# USB.net
KiCad netlist of a schematic drawn in Altium Designer
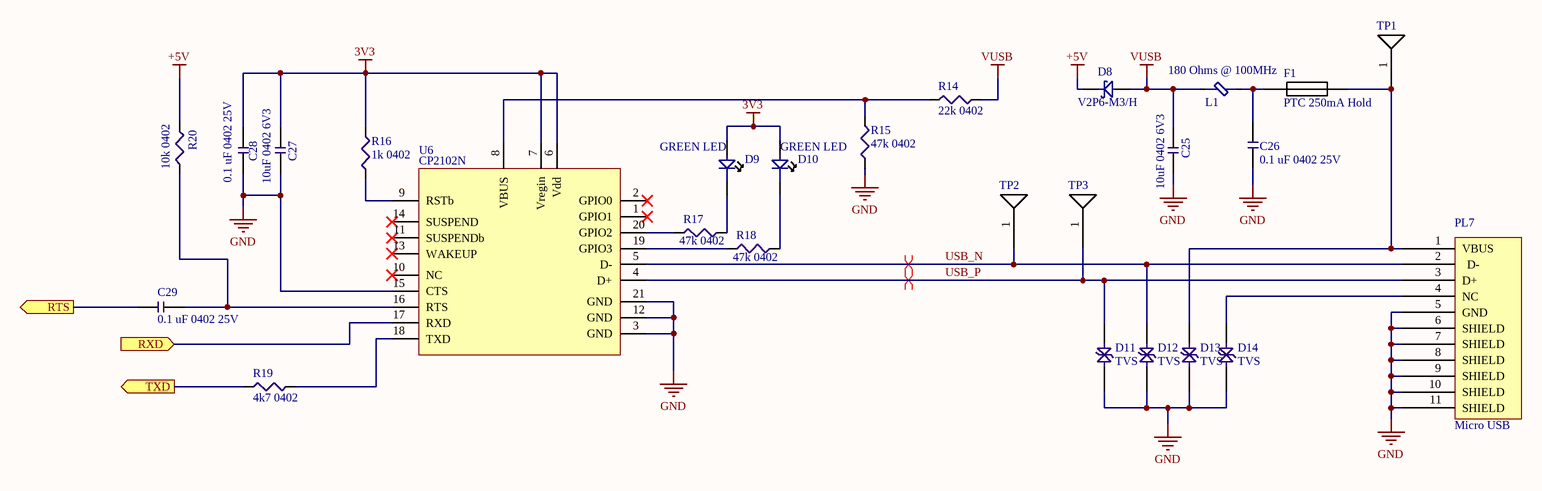
[diagram p0: USB.SchDoc]

(export (version "E")
  (design (tool "Eeschema 10.0.6"))
  (components
    (comp (ref "C25")
      (value "10uF 0402 6V3")
      (footprint "CAP_0402")
      (description "10uF 20% 0402 6V3 X6S")
      (fields (field (name "TOLERANCE") "20%") (field (name "VOLTAGE") "6V3"))
      (libsource (lib "ON Development Vault") (part "Capacitor"))
    )
    (comp (ref "C26")
      (value "0.1 uF 0402 25V")
      (footprint "CAP_0402")
      (description "0.1UF 25V 10% X5R 0402")
      (fields (field (name "TOLERANCE") "10%") (field (name "VOLTAGE") "25V"))
      (libsource (lib "ON Development Vault") (part "Capacitor"))
    )
    (comp (ref "C27")
      (value "10uF 0402 6V3")
      (footprint "CAP_0402")
      (description "10uF 20% 0402 6V3 X6S")
      (fields (field (name "TOLERANCE") "20%") (field (name "VOLTAGE") "6V3"))
      (libsource (lib "ON Development Vault") (part "Capacitor"))
    )
    (comp (ref "C28")
      (value "0.1 uF 0402 25V")
      (footprint "CAP_0402")
      (description "0.1UF 25V 10% X5R 0402")
      (fields (field (name "TOLERANCE") "10%") (field (name "VOLTAGE") "25V"))
      (libsource (lib "ON Development Vault") (part "Capacitor"))
    )
    (comp (ref "C29")
      (value "0.1 uF 0402 25V")
      (footprint "CAP_0402")
      (description "0.1UF 25V 10% X5R 0402")
      (fields (field (name "TOLERANCE") "10%") (field (name "VOLTAGE") "25V"))
      (libsource (lib "ON Development Vault") (part "Capacitor"))
    )
    (comp (ref "D8")
      (value "V2P6-M3/H")
      (footprint "MicroSMP")
      (description "DIODE SCHOTTKY 60V 2A MICROSMP")
      (libsource (lib "ON Development Vault") (part "Schottky"))
    )
    (comp (ref "D9")
      (value "GREEN LED")
      (footprint "0402 LED")
      (description "0402 SMD LED")
      (fields (field (name "MFG. PART NUMBER") "LTST-C281KGKT"))
      (libsource (lib "ON Development Vault") (part "LED"))
    )
    (comp (ref "D10")
      (value "GREEN LED")
      (footprint "0402 LED")
      (description "0402 SMD LED")
      (fields (field (name "MFG. PART NUMBER") "LTST-C281KGKT"))
      (libsource (lib "ON Development Vault") (part "LED"))
    )
    (comp (ref "D11")
      (value "TVS")
      (footprint "RES_0402")
      (description "TVS DIODE 12VC 8A IPP 0402")
      (fields (field (name "MFG. PART NUMBER") "GG040205100N2P"))
      (libsource (lib "ON Development Vault") (part "TVS"))
    )
    (comp (ref "D12")
      (value "TVS")
      (footprint "RES_0402")
      (description "TVS DIODE 12VC 8A IPP 0402")
      (fields (field (name "MFG. PART NUMBER") "GG040205100N2P"))
      (libsource (lib "ON Development Vault") (part "TVS"))
    )
    (comp (ref "D13")
      (value "TVS")
      (footprint "RES_0402")
      (description "TVS DIODE 12VC 8A IPP 0402")
      (fields (field (name "MFG. PART NUMBER") "GG040205100N2P"))
      (libsource (lib "ON Development Vault") (part "TVS"))
    )
    (comp (ref "D14")
      (value "TVS")
      (footprint "RES_0402")
      (description "TVS DIODE 12VC 8A IPP 0402")
      (fields (field (name "MFG. PART NUMBER") "GG040205100N2P"))
      (libsource (lib "ON Development Vault") (part "TVS"))
    )
    (comp (ref "F1")
      (value "PTC 250mA Hold")
      (footprint "PTC Fuse 1206")
      (description "PTC RESET FUSE 24V 250MA 1206")
      (fields (field (name "MFG. PART NUMBER") "0ZCJ0025AF2E"))
      (libsource (lib "ON Development Vault") (part "Fuse"))
    )
    (comp (ref "L1")
      (value "180 Ohms @ 100MHz")
      (footprint "IND_0603")
      (description "FERRITE BEAD 180 OHM 0603 1LN")
      (fields (field (name "MFG. PART NUMBER") "BLM18PG181SN1D"))
      (libsource (lib "ON Development Vault") (part "Ferrite"))
    )
    (comp (ref "PL7")
      (value "Micro USB")
      (footprint "10118193-0001LF Micro USB")
      (description "CONN USB MICRO B RECPT SMT R/A")
      (fields (field (name "MFG. PART NUMBER") "10118193-0001LF"))
      (libsource (lib "ON Development Vault") (part "USB 2.0 Micro usb type B header"))
    )
    (comp (ref "R14")
      (value "22k 0402")
      (footprint "RES_0402")
      (description "RES SMD 22K OHM 1% 1/16W 0402")
      (fields (field (name "POWER") "1/16W") (field (name "TOLERANCE") "1%"))
      (libsource (lib "ON Development Vault") (part "Resistor"))
    )
    (comp (ref "R15")
      (value "47k 0402")
      (footprint "RES_0402")
      (description "RES SMD 47K OHM 1% 1/16W 0402")
      (fields (field (name "POWER") "1/16W") (field (name "TOLERANCE") "1%"))
      (libsource (lib "ON Development Vault") (part "Resistor"))
    )
    (comp (ref "R16")
      (value "1k 0402")
      (footprint "RES_0402")
      (description "RES SMD 1K OHM 1% 1/16W 0402")
      (fields (field (name "POWER") "1/16W") (field (name "TOLERANCE") "1%"))
      (libsource (lib "ON Development Vault") (part "Resistor"))
    )
    (comp (ref "R17")
      (value "47k 0402")
      (footprint "RES_0402")
      (description "RES SMD 47K OHM 1% 1/16W 0402")
      (fields (field (name "POWER") "1/16W") (field (name "TOLERANCE") "1%"))
      (libsource (lib "ON Development Vault") (part "Resistor"))
    )
    (comp (ref "R18")
      (value "47k 0402")
      (footprint "RES_0402")
      (description "RES SMD 47K OHM 1% 1/16W 0402")
      (fields (field (name "POWER") "1/16W") (field (name "TOLERANCE") "1%"))
      (libsource (lib "ON Development Vault") (part "Resistor"))
    )
    (comp (ref "R19")
      (value "4k7 0402")
      (footprint "RES_0402")
      (description "RES SMD 4.7K OHM 1% 1/16W 0402")
      (fields (field (name "POWER") "1/16W") (field (name "TOLERANCE") "1"))
      (libsource (lib "ON Development Vault") (part "Resistor"))
    )
    (comp (ref "R20")
      (value "10k 0402")
      (footprint "RES_0402")
      (description "RES SMD 10K OHM 1% 1/16W 0402")
      (fields (field (name "POWER") "1/16 W") (field (name "TOLERANCE") "1 %"))
      (libsource (lib "ON Development Vault") (part "Resistor"))
    )
    (comp (ref "TP1")
      (value "TestPoint")
      (footprint "1x0mm")
      (description "Testpoint")
      (libsource (lib "ON Development Vault") (part "CMP-ROOT-0006-0.0"))
    )
    (comp (ref "TP2")
      (value "TestPoint")
      (footprint "1x0mm")
      (description "Testpoint")
      (libsource (lib "ON Development Vault") (part "CMP-ROOT-0006-0.0"))
    )
    (comp (ref "TP3")
      (value "TestPoint")
      (footprint "1x0mm")
      (description "Testpoint")
      (libsource (lib "ON Development Vault") (part "CMP-ROOT-0006-0.0"))
    )
    (comp (ref "U6")
      (value "CP2102N")
      (footprint "QFN50P300X300X80_HS-21N")
      (description "IC BRIDGE USB TO UART 20QFN")
      (fields (field (name "MFG. PART NUMBER") "CP2102N-A01-GQFN20"))
      (libsource (lib "ON Development Vault") (part "CP2102N-A01-GQFN20"))
    )
  )
  (nets
    (net (code "1") (name "+5V") (class "Default")
      (node (ref "D8") (pin "2") (pinfunction "2_2") (pintype "passive"))
      (node (ref "R20") (pin "2") (pinfunction "2_2") (pintype "passive"))
    )
    (net (code "2") (name "/RTS") (class "Default")
      (node (ref "C29") (pin "2") (pinfunction "2_2") (pintype "passive"))
    )
    (net (code "3") (name "/RXD") (class "Default")
      (node (ref "U6") (pin "17") (pinfunction "RXD_17") (pintype "passive"))
    )
    (net (code "4") (name "/TXD") (class "Default")
      (node (ref "R19") (pin "2") (pinfunction "2_2") (pintype "passive"))
    )
    (net (code "5") (name "/USB_N") (class "Default")
      (node (ref "D12") (pin "2") (pinfunction "Cathode_2") (pintype "passive"))
      (node (ref "PL7") (pin "2") (pinfunction "D-_2") (pintype "passive"))
      (node (ref "TP2") (pin "1") (pinfunction "0_1") (pintype "passive"))
      (node (ref "U6") (pin "5") (pinfunction "D-_5") (pintype "passive"))
    )
    (net (code "6") (name "/USB_P") (class "Default")
      (node (ref "D11") (pin "2") (pinfunction "Cathode_2") (pintype "passive"))
      (node (ref "PL7") (pin "3") (pinfunction "D+_3") (pintype "passive"))
      (node (ref "TP3") (pin "1") (pinfunction "0_1") (pintype "passive"))
      (node (ref "U6") (pin "4") (pinfunction "D+_4") (pintype "passive"))
    )
    (net (code "7") (name "3V3") (class "Default")
      (node (ref "C27") (pin "2") (pinfunction "2_2") (pintype "passive"))
      (node (ref "C28") (pin "2") (pinfunction "2_2") (pintype "passive"))
      (node (ref "D10") (pin "1") (pinfunction "1_1") (pintype "passive"))
      (node (ref "D9") (pin "1") (pinfunction "1_1") (pintype "passive"))
      (node (ref "R16") (pin "2") (pinfunction "2_2") (pintype "passive"))
      (node (ref "U6") (pin "6") (pinfunction "Vdd_6") (pintype "passive"))
      (node (ref "U6") (pin "7") (pinfunction "Vregin_7") (pintype "passive"))
    )
    (net (code "8") (name "GND") (class "Default")
      (node (ref "C25") (pin "1") (pinfunction "1_1") (pintype "passive"))
      (node (ref "C26") (pin "1") (pinfunction "1_1") (pintype "passive"))
      (node (ref "C27") (pin "1") (pinfunction "1_1") (pintype "passive"))
      (node (ref "C28") (pin "1") (pinfunction "1_1") (pintype "passive"))
      (node (ref "D11") (pin "1") (pinfunction "Anode_1") (pintype "passive"))
      (node (ref "D12") (pin "1") (pinfunction "Anode_1") (pintype "passive"))
      (node (ref "D13") (pin "1") (pinfunction "Anode_1") (pintype "passive"))
      (node (ref "D14") (pin "1") (pinfunction "Anode_1") (pintype "passive"))
      (node (ref "PL7") (pin "10") (pinfunction "SHIELD_10") (pintype "passive"))
      (node (ref "PL7") (pin "11") (pinfunction "SHIELD_11") (pintype "passive"))
      (node (ref "PL7") (pin "5") (pinfunction "GND_5") (pintype "passive"))
      (node (ref "PL7") (pin "6") (pinfunction "SHIELD_6") (pintype "passive"))
      (node (ref "PL7") (pin "7") (pinfunction "SHIELD_7") (pintype "passive"))
      (node (ref "PL7") (pin "8") (pinfunction "SHIELD_8") (pintype "passive"))
      (node (ref "PL7") (pin "9") (pinfunction "SHIELD_9") (pintype "passive"))
      (node (ref "R15") (pin "1") (pinfunction "1_1") (pintype "passive"))
      (node (ref "U6") (pin "12") (pinfunction "GND_12") (pintype "passive"))
      (node (ref "U6") (pin "15") (pinfunction "CTS_15") (pintype "passive"))
      (node (ref "U6") (pin "21") (pinfunction "GND_21") (pintype "passive"))
      (node (ref "U6") (pin "3") (pinfunction "GND_3") (pintype "passive"))
    )
    (net (code "9") (name "Net-(C26-Pad2)") (class "Default")
      (node (ref "C26") (pin "2") (pinfunction "2_2") (pintype "passive"))
      (node (ref "F1") (pin "1") (pinfunction "1_1") (pintype "passive"))
      (node (ref "L1") (pin "2") (pinfunction "2_2") (pintype "passive"))
    )
    (net (code "10") (name "Net-(D9-Pad2)") (class "Default")
      (node (ref "D9") (pin "2") (pinfunction "2_2") (pintype "passive"))
      (node (ref "R17") (pin "1") (pinfunction "1_1") (pintype "passive"))
    )
    (net (code "11") (name "Net-(D10-Pad2)") (class "Default")
      (node (ref "D10") (pin "2") (pinfunction "2_2") (pintype "passive"))
      (node (ref "R18") (pin "1") (pinfunction "1_1") (pintype "passive"))
    )
    (net (code "12") (name "Net-(D13-Cathode)") (class "Default")
      (node (ref "D13") (pin "2") (pinfunction "Cathode_2") (pintype "passive"))
      (node (ref "F1") (pin "2") (pinfunction "2_2") (pintype "passive"))
      (node (ref "PL7") (pin "1") (pinfunction "VBUS_1") (pintype "passive"))
      (node (ref "TP1") (pin "1") (pinfunction "0_1") (pintype "passive"))
    )
    (net (code "13") (name "Net-(D14-Cathode)") (class "Default")
      (node (ref "D14") (pin "2") (pinfunction "Cathode_2") (pintype "passive"))
      (node (ref "PL7") (pin "4") (pinfunction "NC_4") (pintype "passive"))
    )
    (net (code "14") (name "Net-(U6-GPIO2)") (class "Default")
      (node (ref "R17") (pin "2") (pinfunction "2_2") (pintype "passive"))
      (node (ref "U6") (pin "20") (pinfunction "GPIO2_20") (pintype "passive"))
    )
    (net (code "15") (name "Net-(U6-GPIO3)") (class "Default")
      (node (ref "R18") (pin "2") (pinfunction "2_2") (pintype "passive"))
      (node (ref "U6") (pin "19") (pinfunction "GPIO3_19") (pintype "passive"))
    )
    (net (code "16") (name "Net-(U6-RSTb)") (class "Default")
      (node (ref "R16") (pin "1") (pinfunction "1_1") (pintype "passive"))
      (node (ref "U6") (pin "9") (pinfunction "RSTb_9") (pintype "passive"))
    )
    (net (code "17") (name "Net-(U6-RTS)") (class "Default")
      (node (ref "C29") (pin "1") (pinfunction "1_1") (pintype "passive"))
      (node (ref "R20") (pin "1") (pinfunction "1_1") (pintype "passive"))
      (node (ref "U6") (pin "16") (pinfunction "RTS_16") (pintype "passive"))
    )
    (net (code "18") (name "Net-(U6-TXD)") (class "Default")
      (node (ref "R19") (pin "1") (pinfunction "1_1") (pintype "passive"))
      (node (ref "U6") (pin "18") (pinfunction "TXD_18") (pintype "passive"))
    )
    (net (code "19") (name "Net-(U6-VBUS)") (class "Default")
      (node (ref "R14") (pin "1") (pinfunction "1_1") (pintype "passive"))
      (node (ref "R15") (pin "2") (pinfunction "2_2") (pintype "passive"))
      (node (ref "U6") (pin "8") (pinfunction "VBUS_8") (pintype "passive"))
    )
    (net (code "20") (name "VUSB") (class "Default")
      (node (ref "C25") (pin "2") (pinfunction "2_2") (pintype "passive"))
      (node (ref "D8") (pin "1") (pinfunction "1_1") (pintype "passive"))
      (node (ref "L1") (pin "1") (pinfunction "1_1") (pintype "passive"))
      (node (ref "R14") (pin "2") (pinfunction "2_2") (pintype "passive"))
    )
    (net (code "21") (name "unconnected-(U6-GPIO0-Pad2)") (class "Default")
      (node (ref "U6") (pin "2") (pinfunction "GPIO0_2") (pintype "passive+no_connect"))
    )
    (net (code "22") (name "unconnected-(U6-GPIO1-Pad1)") (class "Default")
      (node (ref "U6") (pin "1") (pinfunction "GPIO1_1") (pintype "passive+no_connect"))
    )
    (net (code "23") (name "unconnected-(U6-NC-Pad10)") (class "Default")
      (node (ref "U6") (pin "10") (pinfunction "NC_10") (pintype "passive+no_connect"))
    )
    (net (code "24") (name "unconnected-(U6-SUSPEND-Pad14)") (class "Default")
      (node (ref "U6") (pin "14") (pinfunction "SUSPEND_14") (pintype "passive+no_connect"))
    )
    (net (code "25") (name "unconnected-(U6-SUSPENDb-Pad11)") (class "Default")
      (node (ref "U6") (pin "11") (pinfunction "SUSPENDb_11") (pintype "passive+no_connect"))
    )
    (net (code "26") (name "unconnected-(U6-WAKEUP-Pad13)") (class "Default")
      (node (ref "U6") (pin "13") (pinfunction "WAKEUP_13") (pintype "passive+no_connect"))
    )
  )
)
